# IDCI_WifiNode_PWR.net
KiCad netlist of a schematic drawn in Altium Designer
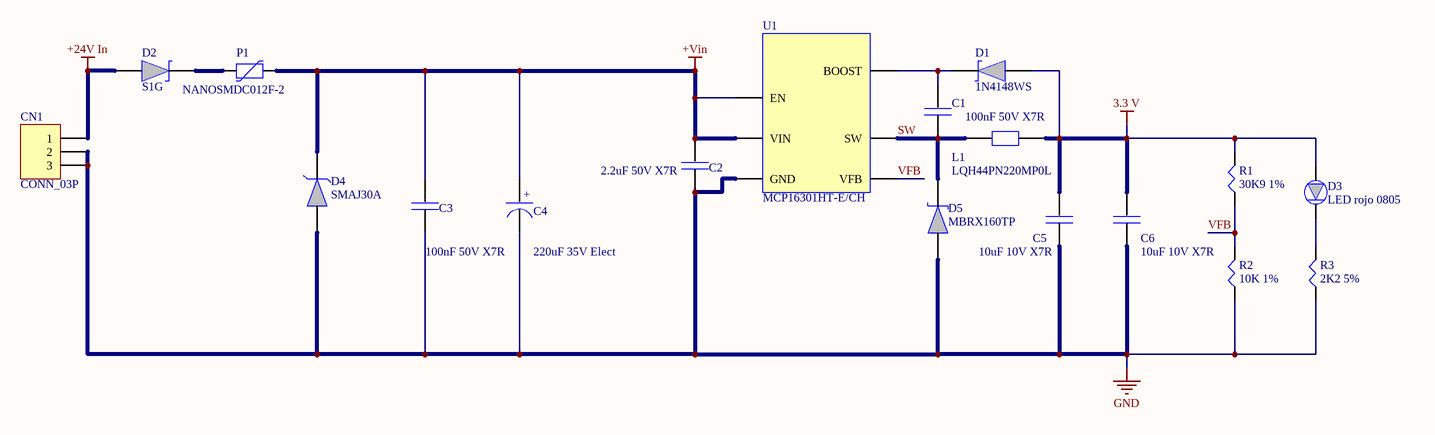
[diagram p0: IDCI_WifiNode_PWR.SchDoc]

(export (version "E")
  (design (tool "Eeschema 10.0.6"))
  (components
    (comp (ref "C1")
      (value "100nF 50V X7R")
      (footprint "C_0805")
      (description "100nF x 50v")
      (libsource (lib "IDCI_WifiNode_2_R00") (part "Capacitor"))
    )
    (comp (ref "C2")
      (value "2.2uF 50V X7R")
      (footprint "C_220ufx35V")
      (description "100nF x 50v")
      (libsource (lib "IDCI_WifiNode_2_R00") (part "Capacitor"))
    )
    (comp (ref "C3")
      (value "100nF 50V X7R")
      (footprint "C_0805")
      (description "100nF x 50v")
      (libsource (lib "IDCI_WifiNode_2_R00") (part "Capacitor"))
    )
    (comp (ref "C4")
      (value "220uF 35V Elect")
      (footprint "C_220ufx35V")
      (description "Capacitor polarizado")
      (libsource (lib "IDCI_WifiNode_2_R00") (part "POL_CAP"))
    )
    (comp (ref "C5")
      (value "10uF 10V X7R")
      (footprint "C_0805")
      (description "100nF x 50v")
      (libsource (lib "IDCI_WifiNode_2_R00") (part "Capacitor"))
    )
    (comp (ref "C6")
      (value "10uF 10V X7R")
      (footprint "C_0805")
      (description "100nF x 50v")
      (libsource (lib "IDCI_WifiNode_2_R00") (part "Capacitor"))
    )
    (comp (ref "CN1")
      (value "CONN_03P")
      (footprint "JACK_2.5mm_F")
      (description "Connector Generic 3 Vias")
      (libsource (lib "IDCI_WifiNode_2_R00") (part "CONN_03P"))
    )
    (comp (ref "D1")
      (value "1N4148WS")
      (footprint "Diode_SOD-323")
      (libsource (lib "IDCI_WifiNode_2_R00") (part "TVS_DIODE"))
    )
    (comp (ref "D2")
      (value "S1G")
      (footprint "DIODE_SMA")
      (libsource (lib "IDCI_WifiNode_2_R00") (part "TVS_DIODE"))
    )
    (comp (ref "D3")
      (value "LED rojo 0805")
      (footprint "LED_0805")
      (libsource (lib "IDCI_WifiNode_2_R00") (part "LED_DIODE"))
    )
    (comp (ref "D4")
      (value "SMAJ30A")
      (footprint "DIODE_SMA")
      (libsource (lib "IDCI_WifiNode_2_R00") (part "ZENER_DIODE"))
    )
    (comp (ref "D5")
      (value "MBRX160TP")
      (footprint "Diode_SOD-123")
      (libsource (lib "IDCI_WifiNode_2_R00") (part "TVS_DIODE"))
    )
    (comp (ref "L1")
      (value "LQH44PN220MP0L")
      (footprint "Inductor_4040")
      (description "Inductor")
      (libsource (lib "IDCI_WifiNode_2_R00") (part "Inductor"))
    )
    (comp (ref "P1")
      (value "NANOSMDC012F-2")
      (footprint "Poly_1206")
      (description "Polyswitch")
      (libsource (lib "IDCI_WifiNode_2_R00") (part "Polyswitch"))
    )
    (comp (ref "R1")
      (value "30K9 1%")
      (footprint "R_0805")
      (libsource (lib "IDCI_WifiNode_2_R00") (part "Resistor"))
    )
    (comp (ref "R2")
      (value "10K 1%")
      (footprint "R_0805")
      (libsource (lib "IDCI_WifiNode_2_R00") (part "Resistor"))
    )
    (comp (ref "R3")
      (value "2K2 5%")
      (footprint "R_0805")
      (libsource (lib "IDCI_WifiNode_2_R00") (part "Resistor"))
    )
    (comp (ref "U1")
      (value "MCP16301HT-E/CH")
      (footprint "IC_SOT23-6")
      (description "Driver Switching")
      (libsource (lib "IDCI_WifiNode_2_R00") (part "Integrado"))
    )
  )
  (nets
    (net (code "1") (name "+24V In") (class "Default")
      (node (ref "CN1") (pin "1") (pinfunction "1_1") (pintype "passive"))
      (node (ref "D2") (pin "1") (pinfunction "1_1") (pintype "passive"))
    )
    (net (code "2") (name "+Vin") (class "Default")
      (node (ref "C2") (pin "1") (pinfunction "1_1") (pintype "passive"))
      (node (ref "C3") (pin "1") (pinfunction "1_1") (pintype "passive"))
      (node (ref "C4") (pin "1") (pinfunction "1_1") (pintype "passive"))
      (node (ref "D4") (pin "2") (pinfunction "2_2") (pintype "passive"))
      (node (ref "P1") (pin "2") (pinfunction "2_2") (pintype "passive"))
      (node (ref "U1") (pin "4") (pinfunction "EN_4") (pintype "passive"))
      (node (ref "U1") (pin "5") (pinfunction "VIN_5") (pintype "passive"))
    )
    (net (code "3") (name "/SW") (class "Default")
      (node (ref "C1") (pin "2") (pinfunction "2_2") (pintype "passive"))
      (node (ref "D5") (pin "2") (pinfunction "2_2") (pintype "passive"))
      (node (ref "L1") (pin "1") (pinfunction "1_1") (pintype "passive"))
      (node (ref "U1") (pin "6") (pinfunction "SW_6") (pintype "passive"))
    )
    (net (code "4") (name "/VFB") (class "Default")
      (node (ref "R1") (pin "1") (pinfunction "1_1") (pintype "passive"))
      (node (ref "R2") (pin "2") (pinfunction "2_2") (pintype "passive"))
      (node (ref "U1") (pin "3") (pinfunction "VFB_3") (pintype "passive"))
    )
    (net (code "5") (name "3.3 V") (class "Default")
      (node (ref "C5") (pin "1") (pinfunction "1_1") (pintype "passive"))
      (node (ref "C6") (pin "1") (pinfunction "1_1") (pintype "passive"))
      (node (ref "D1") (pin "1") (pinfunction "1_1") (pintype "passive"))
      (node (ref "D3") (pin "1") (pinfunction "1_1") (pintype "passive"))
      (node (ref "L1") (pin "2") (pinfunction "2_2") (pintype "passive"))
      (node (ref "R1") (pin "2") (pinfunction "2_2") (pintype "passive"))
    )
    (net (code "6") (name "GND") (class "Default")
      (node (ref "C2") (pin "2") (pinfunction "2_2") (pintype "passive"))
      (node (ref "C3") (pin "2") (pinfunction "2_2") (pintype "passive"))
      (node (ref "C4") (pin "2") (pinfunction "2_2") (pintype "passive"))
      (node (ref "C5") (pin "2") (pinfunction "2_2") (pintype "passive"))
      (node (ref "C6") (pin "2") (pinfunction "2_2") (pintype "passive"))
      (node (ref "CN1") (pin "2") (pinfunction "2_2") (pintype "passive"))
      (node (ref "CN1") (pin "3") (pinfunction "3_3") (pintype "passive"))
      (node (ref "D4") (pin "1") (pinfunction "1_1") (pintype "passive"))
      (node (ref "D5") (pin "1") (pinfunction "1_1") (pintype "passive"))
      (node (ref "R2") (pin "1") (pinfunction "1_1") (pintype "passive"))
      (node (ref "R3") (pin "1") (pinfunction "1_1") (pintype "passive"))
      (node (ref "U1") (pin "2") (pinfunction "GND_2") (pintype "passive"))
    )
    (net (code "7") (name "Net-(D2-Pad2)") (class "Default")
      (node (ref "D2") (pin "2") (pinfunction "2_2") (pintype "passive"))
      (node (ref "P1") (pin "1") (pinfunction "1_1") (pintype "passive"))
    )
    (net (code "8") (name "Net-(D3-Pad2)") (class "Default")
      (node (ref "D3") (pin "2") (pinfunction "2_2") (pintype "passive"))
      (node (ref "R3") (pin "2") (pinfunction "2_2") (pintype "passive"))
    )
    (net (code "9") (name "Net-(U1-BOOST)") (class "Default")
      (node (ref "C1") (pin "1") (pinfunction "1_1") (pintype "passive"))
      (node (ref "D1") (pin "2") (pinfunction "2_2") (pintype "passive"))
      (node (ref "U1") (pin "1") (pinfunction "BOOST_1") (pintype "passive"))
    )
  )
)
